# RF1_RS485v3.net
KiCad netlist of a schematic drawn in EAGLE
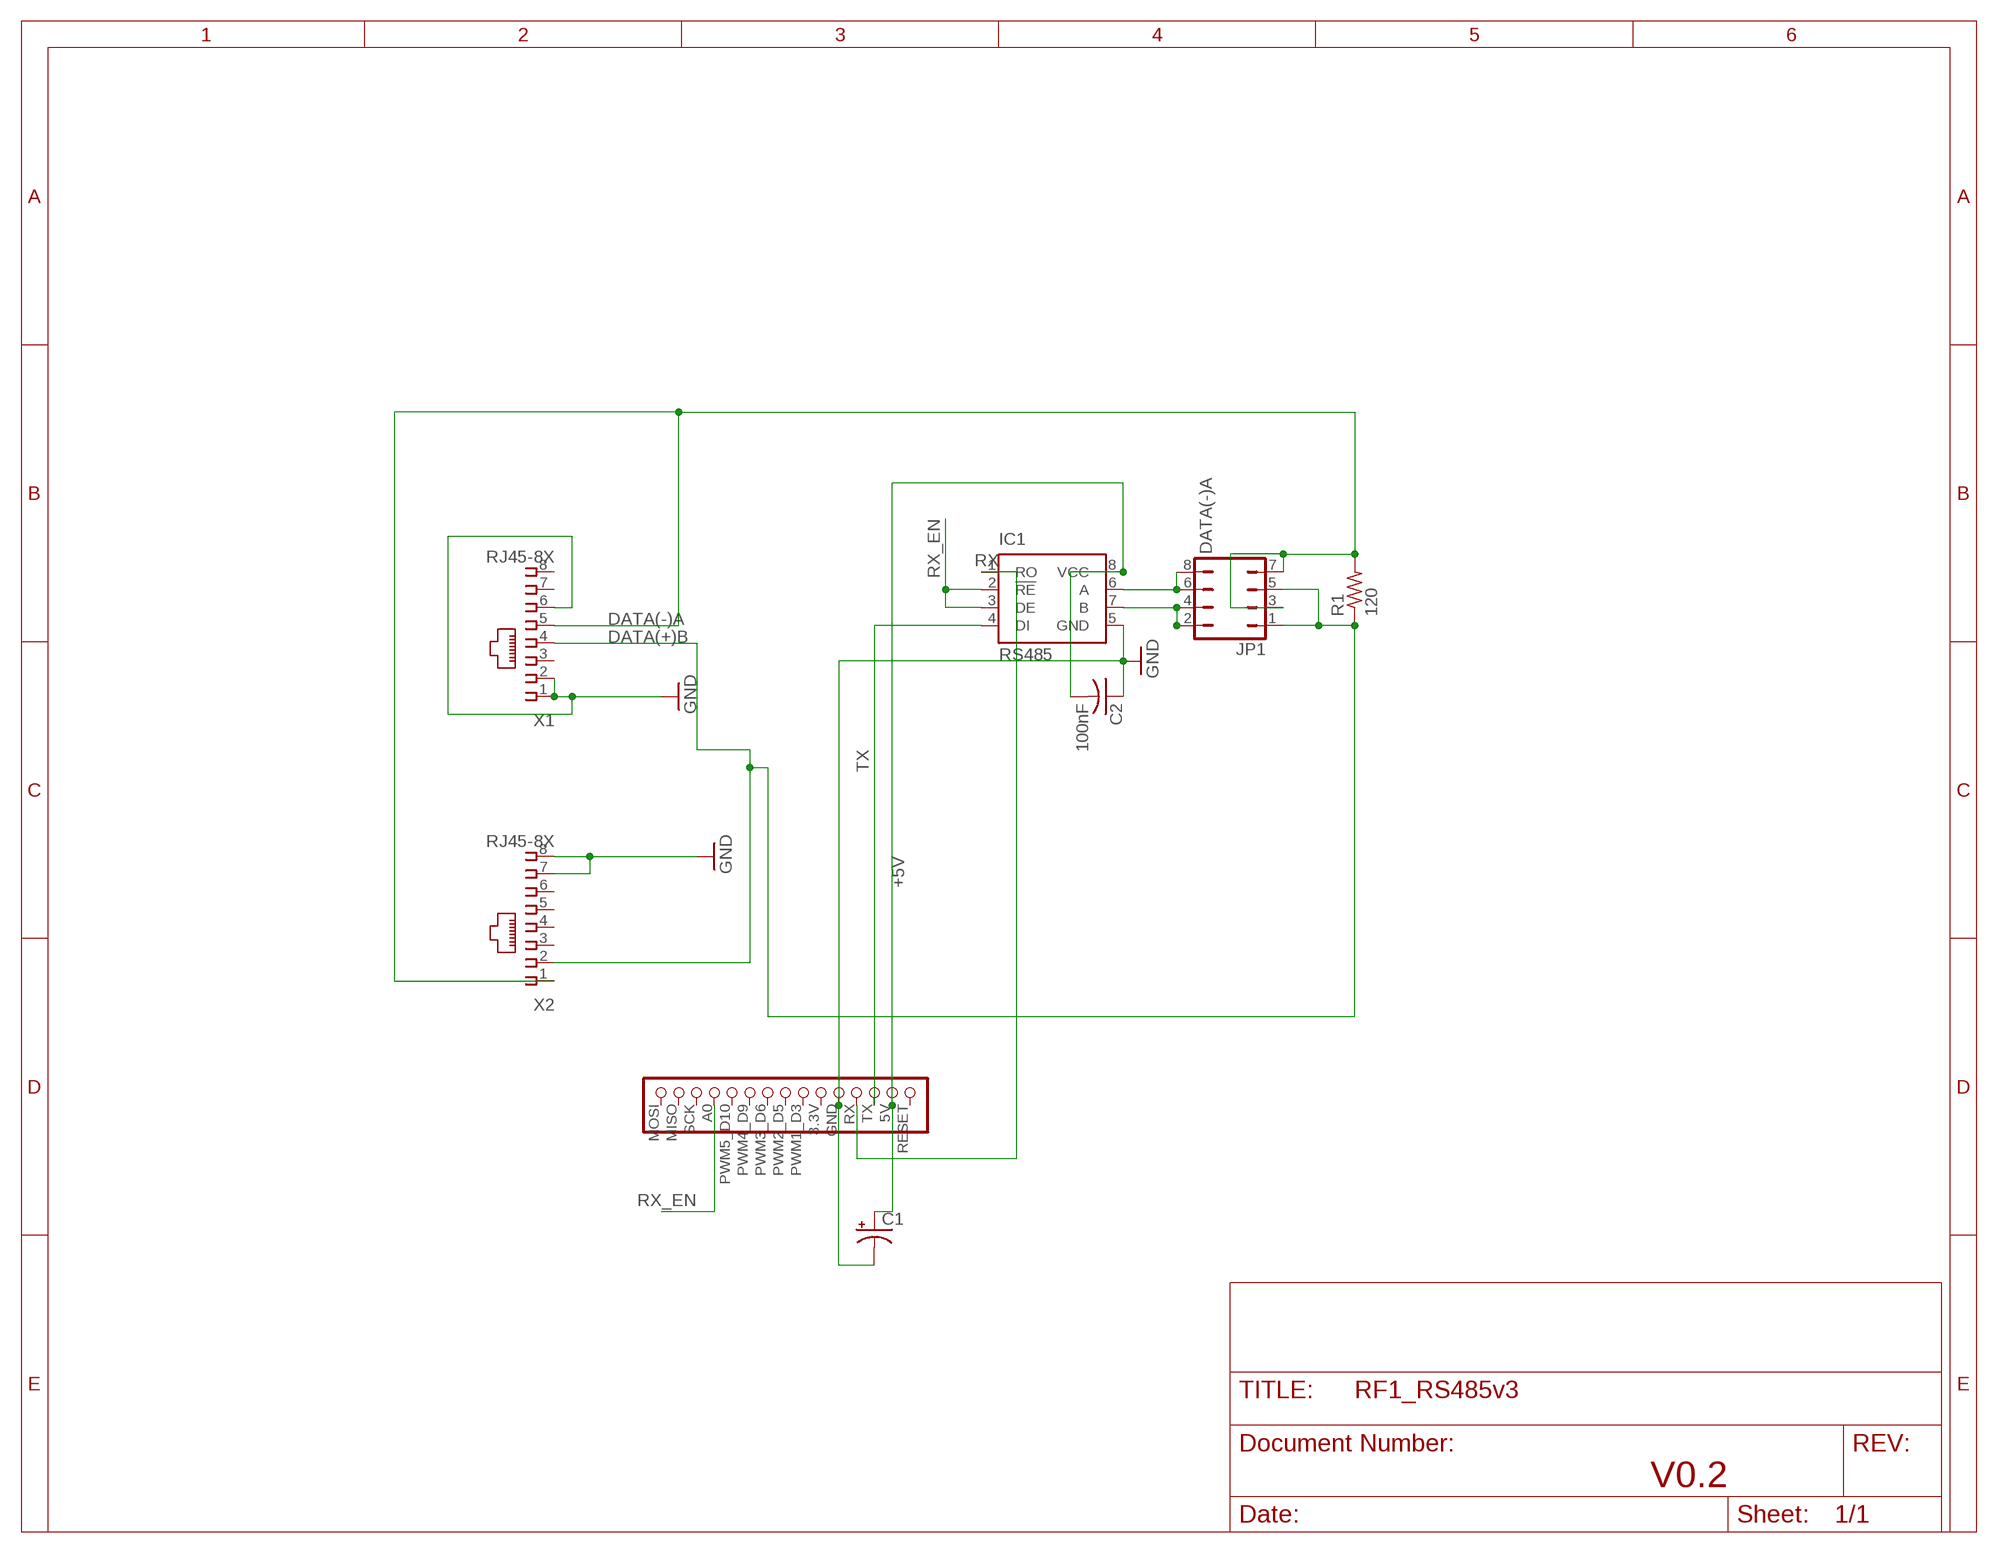
[diagram p0: schematic, sheet 1]

(export (version "E")
  (design (tool "Eeschema 10.0.6"))
  (components
    (comp (ref "C1")
      (value "CPOL-USE5-5")
      (footprint "eagle-import:E5-5")
      (libsource (lib "eagle-import") (part "CPOL-USE5-5"))
    )
    (comp (ref "C2")
      (value "100nF")
      (footprint "eagle-import:C025-024X044")
      (libsource (lib "eagle-import") (part "C-US025-024X044"))
    )
    (comp (ref "IC1")
      (value "RS485")
      (footprint "eagle-import:DIL08")
      (libsource (lib "eagle-import") (part "LTC485N"))
    )
    (comp (ref "JP1")
      (value "JP4Q")
      (footprint "eagle-import:JP4Q")
      (libsource (lib "eagle-import") (part "JP4Q"))
    )
    (comp (ref "R1")
      (value "120")
      (footprint "eagle-import:0805-THM")
      (libsource (lib "eagle-import") (part "R-US_FLIPFLOP"))
    )
    (comp (ref "U$1")
      (value "RF1_HEADER_LEFT")
      (footprint "eagle-import:RF1_LEFTHEADER_ONLY")
      (libsource (lib "eagle-import") (part "RF1_HEADER_LEFT"))
    )
    (comp (ref "X1")
      (value "RJ45-8X")
      (footprint "eagle-import:RJ45-NO-SHIELD")
      (libsource (lib "eagle-import") (part "RJ45-8X"))
    )
    (comp (ref "X2")
      (value "RJ45-8X")
      (footprint "eagle-import:RJ45-NO-SHIELD")
      (libsource (lib "eagle-import") (part "RJ45-8X"))
    )
  )
  (nets
    (net (code "1") (name "/+5V") (class "Default")
      (node (ref "C1") (pin "+") (pinfunction "+_+") (pintype "passive"))
      (node (ref "C2") (pin "2") (pinfunction "2_2") (pintype "passive"))
      (node (ref "IC1") (pin "8") (pinfunction "VCC_8") (pintype "input"))
      (node (ref "U$1") (pin "5V") (pinfunction "5V_5V") (pintype "passive"))
    )
    (net (code "2") (name "/DATA(+)B") (class "Default")
      (node (ref "JP1") (pin "1") (pinfunction "1_1") (pintype "passive"))
      (node (ref "JP1") (pin "5") (pinfunction "5_5") (pintype "passive"))
      (node (ref "R1") (pin "1") (pinfunction "1_1") (pintype "passive"))
      (node (ref "X1") (pin "4") (pinfunction "4_4") (pintype "passive"))
      (node (ref "X2") (pin "2") (pinfunction "2_2") (pintype "passive"))
    )
    (net (code "3") (name "/DATA(-)A") (class "Default")
      (node (ref "JP1") (pin "3") (pinfunction "3_3") (pintype "passive"))
      (node (ref "JP1") (pin "7") (pinfunction "7_7") (pintype "passive"))
      (node (ref "R1") (pin "2") (pinfunction "2_2") (pintype "passive"))
      (node (ref "X1") (pin "5") (pinfunction "5_5") (pintype "passive"))
      (node (ref "X2") (pin "1") (pinfunction "1_1") (pintype "passive"))
    )
    (net (code "4") (name "/RX") (class "Default")
      (node (ref "IC1") (pin "1") (pinfunction "RO_1") (pintype "output"))
      (node (ref "U$1") (pin "RX") (pinfunction "RX_RX") (pintype "passive"))
    )
    (net (code "5") (name "/RX_EN") (class "Default")
      (node (ref "IC1") (pin "2") (pinfunction "~{RE}_2") (pintype "input"))
      (node (ref "IC1") (pin "3") (pinfunction "DE_3") (pintype "input"))
      (node (ref "U$1") (pin "A0") (pinfunction "PC0_A0") (pintype "passive"))
    )
    (net (code "6") (name "/TX") (class "Default")
      (node (ref "IC1") (pin "4") (pinfunction "DI_4") (pintype "input"))
      (node (ref "U$1") (pin "TX") (pinfunction "TX_TX") (pintype "passive"))
    )
    (net (code "7") (name "GND") (class "Default")
      (node (ref "C1") (pin "-") (pinfunction "-_-") (pintype "passive"))
      (node (ref "C2") (pin "1") (pinfunction "1_1") (pintype "passive"))
      (node (ref "IC1") (pin "5") (pinfunction "GND_5") (pintype "input"))
      (node (ref "U$1") (pin "GND") (pinfunction "GND_GND") (pintype "passive"))
      (node (ref "X1") (pin "1") (pinfunction "1_1") (pintype "passive"))
      (node (ref "X1") (pin "2") (pinfunction "2_2") (pintype "passive"))
      (node (ref "X1") (pin "6") (pinfunction "6_6") (pintype "passive"))
      (node (ref "X2") (pin "7") (pinfunction "7_7") (pintype "passive"))
      (node (ref "X2") (pin "8") (pinfunction "8_8") (pintype "passive"))
    )
    (net (code "8") (name "Net-(IC1-A)") (class "Default")
      (node (ref "IC1") (pin "6") (pinfunction "A_6") (pintype "bidirectional"))
      (node (ref "JP1") (pin "6") (pinfunction "6_6") (pintype "passive"))
      (node (ref "JP1") (pin "8") (pinfunction "8_8") (pintype "passive"))
    )
    (net (code "9") (name "Net-(IC1-B)") (class "Default")
      (node (ref "IC1") (pin "7") (pinfunction "B_7") (pintype "bidirectional"))
      (node (ref "JP1") (pin "2") (pinfunction "2_2") (pintype "passive"))
      (node (ref "JP1") (pin "4") (pinfunction "4_4") (pintype "passive"))
    )
    (net (code "10") (name "unconnected-(U$1-PWM1-PadPWM1_D3)") (class "Default")
      (node (ref "U$1") (pin "PWM1_D3") (pinfunction "PWM1_PWM1_D3") (pintype "passive"))
    )
    (net (code "11") (name "unconnected-(U$1-PWM2-PadPWM2_D5)") (class "Default")
      (node (ref "U$1") (pin "PWM2_D5") (pinfunction "PWM2_PWM2_D5") (pintype "passive"))
    )
    (net (code "12") (name "unconnected-(U$1-PWM3-PadPWM3_D6)") (class "Default")
      (node (ref "U$1") (pin "PWM3_D6") (pinfunction "PWM3_PWM3_D6") (pintype "passive"))
    )
    (net (code "13") (name "unconnected-(U$1-PWM4-PadPWM4_D9)") (class "Default")
      (node (ref "U$1") (pin "PWM4_D9") (pinfunction "PWM4_PWM4_D9") (pintype "passive"))
    )
    (net (code "14") (name "unconnected-(U$1-PWM5-PadPWM5_D10)") (class "Default")
      (node (ref "U$1") (pin "PWM5_D10") (pinfunction "PWM5_PWM5_D10") (pintype "passive"))
    )
    (net (code "15") (name "unconnected-(U$1-Pad3.3V)") (class "Default")
      (node (ref "U$1") (pin "3.3V") (pinfunction "3.3V_3.3V") (pintype "passive"))
    )
    (net (code "16") (name "unconnected-(U$1-PadMISO)") (class "Default")
      (node (ref "U$1") (pin "MISO") (pinfunction "MISO_MISO") (pintype "passive"))
    )
    (net (code "17") (name "unconnected-(U$1-PadMOSI)") (class "Default")
      (node (ref "U$1") (pin "MOSI") (pinfunction "MOSI_MOSI") (pintype "passive"))
    )
    (net (code "18") (name "unconnected-(U$1-PadRESET)") (class "Default")
      (node (ref "U$1") (pin "RESET") (pinfunction "RESET_RESET") (pintype "passive"))
    )
    (net (code "19") (name "unconnected-(U$1-PadSCK)") (class "Default")
      (node (ref "U$1") (pin "SCK") (pinfunction "SCK_SCK") (pintype "passive"))
    )
    (net (code "20") (name "unconnected-(X1-Pad3)") (class "Default")
      (node (ref "X1") (pin "3") (pinfunction "3_3") (pintype "passive"))
    )
    (net (code "21") (name "unconnected-(X1-Pad7)") (class "Default")
      (node (ref "X1") (pin "7") (pinfunction "7_7") (pintype "passive"))
    )
    (net (code "22") (name "unconnected-(X1-Pad8)") (class "Default")
      (node (ref "X1") (pin "8") (pinfunction "8_8") (pintype "passive"))
    )
    (net (code "23") (name "unconnected-(X2-Pad3)") (class "Default")
      (node (ref "X2") (pin "3") (pinfunction "3_3") (pintype "passive"))
    )
    (net (code "24") (name "unconnected-(X2-Pad4)") (class "Default")
      (node (ref "X2") (pin "4") (pinfunction "4_4") (pintype "passive"))
    )
    (net (code "25") (name "unconnected-(X2-Pad5)") (class "Default")
      (node (ref "X2") (pin "5") (pinfunction "5_5") (pintype "passive"))
    )
    (net (code "26") (name "unconnected-(X2-Pad6)") (class "Default")
      (node (ref "X2") (pin "6") (pinfunction "6_6") (pintype "passive"))
    )
  )
)
